# basic_schematic_interrupt.net
KiCad netlist of a schematic drawn in EAGLE
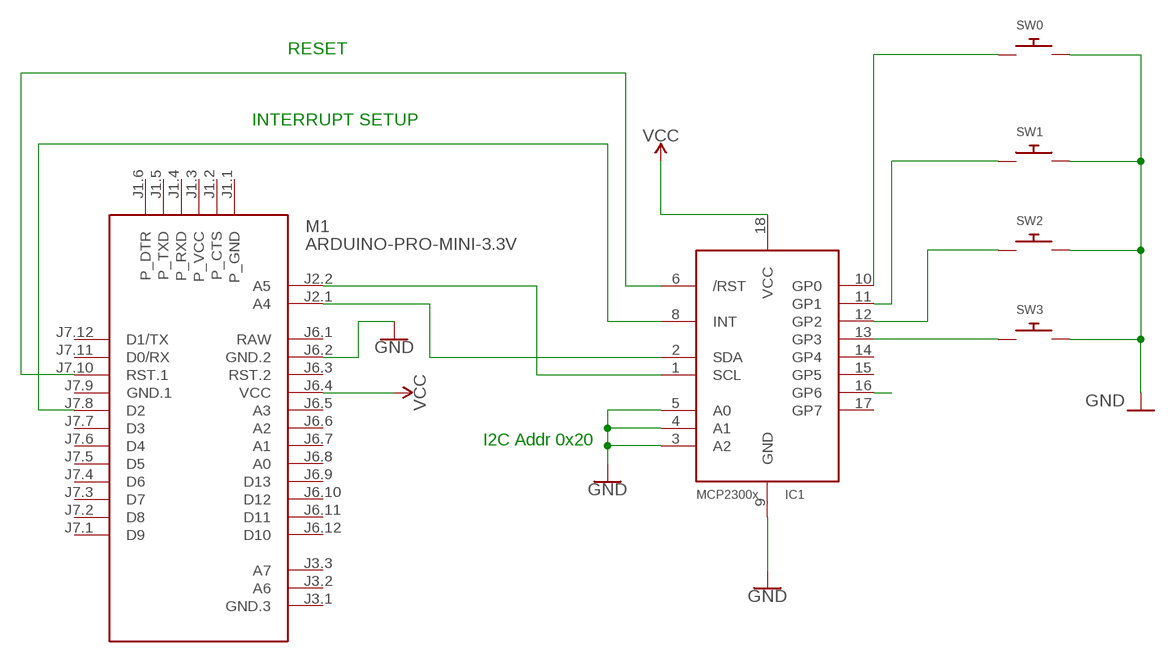
[diagram p0: schematic, sheet 1]

(export (version "E")
  (design (tool "Eeschema 10.0.6"))
  (components
    (comp (ref "IC1")
      (value "MCP23008/SO")
      (footprint "eagle-import:SO18W")
      (libsource (lib "eagle-import") (part "MCP23008/SO"))
    )
    (comp (ref "M1")
      (value "ARDUINO-PRO-MINI-3.3V")
      (footprint "eagle-import:ARDUINO-PRO-MINI")
      (libsource (lib "eagle-import") (part "ARDUINO-PRO-MINI-3.3V"))
    )
    (comp (ref "SW0")
      (value "SWITCH_PUSHBUTTONC&K_KSS")
      (footprint "eagle-import:BTN_CK_KSS")
      (libsource (lib "eagle-import") (part "SWITCH_PUSHBUTTONC&K_KSS"))
    )
    (comp (ref "SW1")
      (value "SWITCH_PUSHBUTTONC&K_KSS")
      (footprint "eagle-import:BTN_CK_KSS")
      (libsource (lib "eagle-import") (part "SWITCH_PUSHBUTTONC&K_KSS"))
    )
    (comp (ref "SW2")
      (value "SWITCH_PUSHBUTTONC&K_KSS")
      (footprint "eagle-import:BTN_CK_KSS")
      (libsource (lib "eagle-import") (part "SWITCH_PUSHBUTTONC&K_KSS"))
    )
    (comp (ref "SW3")
      (value "SWITCH_PUSHBUTTONC&K_KSS")
      (footprint "eagle-import:BTN_CK_KSS")
      (libsource (lib "eagle-import") (part "SWITCH_PUSHBUTTONC&K_KSS"))
    )
  )
  (nets
    (net (code "1") (name "/GND.1") (class "Default")
      (node (ref "M1") (pin "J7.9") (pinfunction "GND.1_J7.9") (pintype "power_in"))
    )
    (net (code "2") (name "/RAW") (class "Default")
      (node (ref "M1") (pin "J6.1") (pinfunction "RAW_J6.1") (pintype "power_in"))
    )
    (net (code "3") (name "GND") (class "Default")
      (node (ref "IC1") (pin "3") (pinfunction "A2_3") (pintype "input"))
      (node (ref "IC1") (pin "4") (pinfunction "A1_4") (pintype "input"))
      (node (ref "IC1") (pin "5") (pinfunction "A0_5") (pintype "input"))
      (node (ref "IC1") (pin "9") (pinfunction "GND_9") (pintype "power_in"))
      (node (ref "M1") (pin "J6.2") (pinfunction "GND.2_J6.2") (pintype "power_in"))
      (node (ref "SW0") (pin "P$2") (pinfunction "P$2_P$2") (pintype "passive"))
      (node (ref "SW1") (pin "P$2") (pinfunction "P$2_P$2") (pintype "passive"))
      (node (ref "SW2") (pin "P$2") (pinfunction "P$2_P$2") (pintype "passive"))
      (node (ref "SW3") (pin "P$2") (pinfunction "P$2_P$2") (pintype "passive"))
    )
    (net (code "4") (name "Net-(IC1-GP0)") (class "Default")
      (node (ref "IC1") (pin "10") (pinfunction "GP0_10") (pintype "bidirectional"))
      (node (ref "SW0") (pin "P$1") (pinfunction "P$1_P$1") (pintype "passive"))
    )
    (net (code "5") (name "Net-(IC1-GP1)") (class "Default")
      (node (ref "IC1") (pin "11") (pinfunction "GP1_11") (pintype "bidirectional"))
      (node (ref "SW1") (pin "P$1") (pinfunction "P$1_P$1") (pintype "passive"))
    )
    (net (code "6") (name "Net-(IC1-GP2)") (class "Default")
      (node (ref "IC1") (pin "12") (pinfunction "GP2_12") (pintype "bidirectional"))
      (node (ref "SW2") (pin "P$1") (pinfunction "P$1_P$1") (pintype "passive"))
    )
    (net (code "7") (name "Net-(IC1-GP3)") (class "Default")
      (node (ref "IC1") (pin "13") (pinfunction "GP3_13") (pintype "bidirectional"))
      (node (ref "SW3") (pin "P$1") (pinfunction "P$1_P$1") (pintype "passive"))
    )
    (net (code "8") (name "Net-(IC1-INT)") (class "Default")
      (node (ref "IC1") (pin "8") (pinfunction "INT_8") (pintype "output"))
      (node (ref "M1") (pin "J7.8") (pinfunction "D2_J7.8") (pintype "bidirectional"))
    )
    (net (code "9") (name "Net-(IC1-SCL)") (class "Default")
      (node (ref "IC1") (pin "1") (pinfunction "SCL_1") (pintype "bidirectional"))
      (node (ref "M1") (pin "J2.2") (pinfunction "A5_J2.2") (pintype "bidirectional"))
    )
    (net (code "10") (name "Net-(IC1-SDA)") (class "Default")
      (node (ref "IC1") (pin "2") (pinfunction "SDA_2") (pintype "bidirectional"))
      (node (ref "M1") (pin "J2.1") (pinfunction "A4_J2.1") (pintype "bidirectional"))
    )
    (net (code "11") (name "Net-(IC1-{slash}RST)") (class "Default")
      (node (ref "IC1") (pin "6") (pinfunction "/RST_6") (pintype "input"))
      (node (ref "M1") (pin "J7.10") (pinfunction "RST.1_J7.10") (pintype "bidirectional"))
    )
    (net (code "12") (name "VCC") (class "Default")
      (node (ref "IC1") (pin "18") (pinfunction "VCC_18") (pintype "power_in"))
      (node (ref "M1") (pin "J6.4") (pinfunction "VCC_J6.4") (pintype "power_in"))
    )
    (net (code "13") (name "unconnected-(IC1-GP4-Pad14)") (class "Default")
      (node (ref "IC1") (pin "14") (pinfunction "GP4_14") (pintype "bidirectional"))
    )
    (net (code "14") (name "unconnected-(IC1-GP5-Pad15)") (class "Default")
      (node (ref "IC1") (pin "15") (pinfunction "GP5_15") (pintype "bidirectional"))
    )
    (net (code "15") (name "unconnected-(IC1-GP6-Pad16)") (class "Default")
      (node (ref "IC1") (pin "16") (pinfunction "GP6_16") (pintype "bidirectional"))
    )
    (net (code "16") (name "unconnected-(IC1-GP7-Pad17)") (class "Default")
      (node (ref "IC1") (pin "17") (pinfunction "GP7_17") (pintype "bidirectional"))
    )
    (net (code "17") (name "unconnected-(M1-A0-PadJ6.8)") (class "Default")
      (node (ref "M1") (pin "J6.8") (pinfunction "A0_J6.8") (pintype "bidirectional"))
    )
    (net (code "18") (name "unconnected-(M1-A1-PadJ6.7)") (class "Default")
      (node (ref "M1") (pin "J6.7") (pinfunction "A1_J6.7") (pintype "bidirectional"))
    )
    (net (code "19") (name "unconnected-(M1-A2-PadJ6.6)") (class "Default")
      (node (ref "M1") (pin "J6.6") (pinfunction "A2_J6.6") (pintype "bidirectional"))
    )
    (net (code "20") (name "unconnected-(M1-A3-PadJ6.5)") (class "Default")
      (node (ref "M1") (pin "J6.5") (pinfunction "A3_J6.5") (pintype "bidirectional"))
    )
    (net (code "21") (name "unconnected-(M1-A6-PadJ3.2)") (class "Default")
      (node (ref "M1") (pin "J3.2") (pinfunction "A6_J3.2") (pintype "bidirectional"))
    )
    (net (code "22") (name "unconnected-(M1-A7-PadJ3.3)") (class "Default")
      (node (ref "M1") (pin "J3.3") (pinfunction "A7_J3.3") (pintype "bidirectional"))
    )
    (net (code "23") (name "unconnected-(M1-D0{slash}RX-PadJ7.11)") (class "Default")
      (node (ref "M1") (pin "J7.11") (pinfunction "D0/RX_J7.11") (pintype "bidirectional"))
    )
    (net (code "24") (name "unconnected-(M1-D1{slash}TX-PadJ7.12)") (class "Default")
      (node (ref "M1") (pin "J7.12") (pinfunction "D1/TX_J7.12") (pintype "bidirectional"))
    )
    (net (code "25") (name "unconnected-(M1-D3-PadJ7.7)") (class "Default")
      (node (ref "M1") (pin "J7.7") (pinfunction "D3_J7.7") (pintype "bidirectional"))
    )
    (net (code "26") (name "unconnected-(M1-D4-PadJ7.6)") (class "Default")
      (node (ref "M1") (pin "J7.6") (pinfunction "D4_J7.6") (pintype "bidirectional"))
    )
    (net (code "27") (name "unconnected-(M1-D5-PadJ7.5)") (class "Default")
      (node (ref "M1") (pin "J7.5") (pinfunction "D5_J7.5") (pintype "bidirectional"))
    )
    (net (code "28") (name "unconnected-(M1-D6-PadJ7.4)") (class "Default")
      (node (ref "M1") (pin "J7.4") (pinfunction "D6_J7.4") (pintype "bidirectional"))
    )
    (net (code "29") (name "unconnected-(M1-D7-PadJ7.3)") (class "Default")
      (node (ref "M1") (pin "J7.3") (pinfunction "D7_J7.3") (pintype "bidirectional"))
    )
    (net (code "30") (name "unconnected-(M1-D8-PadJ7.2)") (class "Default")
      (node (ref "M1") (pin "J7.2") (pinfunction "D8_J7.2") (pintype "bidirectional"))
    )
    (net (code "31") (name "unconnected-(M1-D9-PadJ7.1)") (class "Default")
      (node (ref "M1") (pin "J7.1") (pinfunction "D9_J7.1") (pintype "bidirectional"))
    )
    (net (code "32") (name "unconnected-(M1-D10-PadJ6.12)") (class "Default")
      (node (ref "M1") (pin "J6.12") (pinfunction "D10_J6.12") (pintype "bidirectional"))
    )
    (net (code "33") (name "unconnected-(M1-D11-PadJ6.11)") (class "Default")
      (node (ref "M1") (pin "J6.11") (pinfunction "D11_J6.11") (pintype "bidirectional"))
    )
    (net (code "34") (name "unconnected-(M1-D12-PadJ6.10)") (class "Default")
      (node (ref "M1") (pin "J6.10") (pinfunction "D12_J6.10") (pintype "bidirectional"))
    )
    (net (code "35") (name "unconnected-(M1-D13-PadJ6.9)") (class "Default")
      (node (ref "M1") (pin "J6.9") (pinfunction "D13_J6.9") (pintype "bidirectional"))
    )
    (net (code "36") (name "unconnected-(M1-GND.3-PadJ3.1)") (class "Default")
      (node (ref "M1") (pin "J3.1") (pinfunction "GND.3_J3.1") (pintype "bidirectional"))
    )
    (net (code "37") (name "unconnected-(M1-P_CTS-PadJ1.2)") (class "Default")
      (node (ref "M1") (pin "J1.2") (pinfunction "P_CTS_J1.2") (pintype "bidirectional"))
    )
    (net (code "38") (name "unconnected-(M1-P_DTR-PadJ1.6)") (class "Default")
      (node (ref "M1") (pin "J1.6") (pinfunction "P_DTR_J1.6") (pintype "bidirectional"))
    )
    (net (code "39") (name "unconnected-(M1-P_GND-PadJ1.1)") (class "Default")
      (node (ref "M1") (pin "J1.1") (pinfunction "P_GND_J1.1") (pintype "bidirectional"))
    )
    (net (code "40") (name "unconnected-(M1-P_RXD-PadJ1.4)") (class "Default")
      (node (ref "M1") (pin "J1.4") (pinfunction "P_RXD_J1.4") (pintype "bidirectional"))
    )
    (net (code "41") (name "unconnected-(M1-P_TXD-PadJ1.5)") (class "Default")
      (node (ref "M1") (pin "J1.5") (pinfunction "P_TXD_J1.5") (pintype "bidirectional"))
    )
    (net (code "42") (name "unconnected-(M1-P_VCC-PadJ1.3)") (class "Default")
      (node (ref "M1") (pin "J1.3") (pinfunction "P_VCC_J1.3") (pintype "bidirectional"))
    )
    (net (code "43") (name "unconnected-(M1-RST.2-PadJ6.3)") (class "Default")
      (node (ref "M1") (pin "J6.3") (pinfunction "RST.2_J6.3") (pintype "bidirectional"))
    )
  )
)
